# M_FOC.net
KiCad netlist of a schematic drawn in Altium Designer
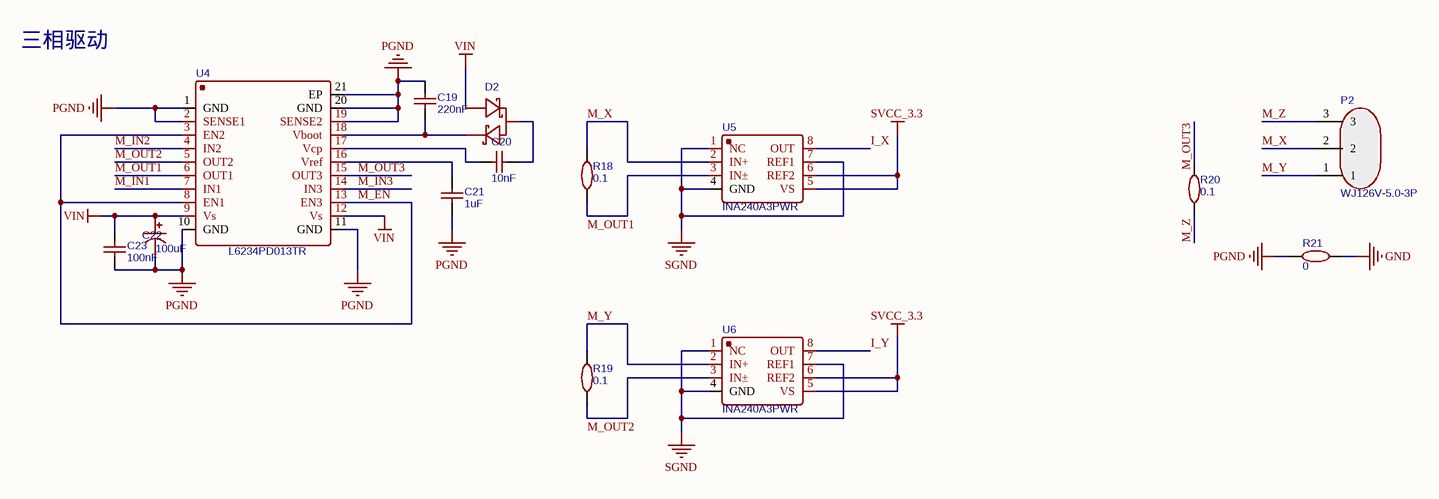
[diagram p0: M_FOC.SchDoc]

(export (version "E")
  (design (tool "Eeschema 10.0.6"))
  (components
    (comp (ref "C19")
      (value "220nF")
      (footprint "C0603")
      (fields
        (field (name "BOM_MANUFACTURER PART") "CC0805KRX7R9BB104")
        (field (name "BOM_SUPPLIER PART") "C49678")
      )
      (libsource (lib "FOC") (part "220nF"))
    )
    (comp (ref "C20")
      (value "10nF")
      (footprint "C0603")
      (fields
        (field (name "BOM_MANUFACTURER PART") "CC0805KRX7R9BB104")
        (field (name "BOM_SUPPLIER PART") "C49678")
      )
      (libsource (lib "FOC") (part "10nF"))
    )
    (comp (ref "C21")
      (value "1uF")
      (footprint "C0603")
      (fields
        (field (name "BOM_MANUFACTURER PART") "CC0805KRX7R9BB104")
        (field (name "BOM_SUPPLIER PART") "C49678")
      )
      (libsource (lib "FOC") (part "1uF"))
    )
    (comp (ref "C22")
      (value "100uF")
      (footprint "CAP-SMD_BD6.3-L6.6-W6.6-RD")
      (description "电解电容")
      (fields
        (field (name "BOM_MANUFACTURER PART") "RVE1V101M0607")
        (field (name "BOM_SUPPLIER PART") "C99837")
      )
      (libsource (lib "FOC") (part "100uF"))
    )
    (comp (ref "C23")
      (value "100nF")
      (footprint "C0603")
      (fields
        (field (name "BOM_MANUFACTURER PART") "CC0805KRX7R9BB104")
        (field (name "BOM_SUPPLIER PART") "C49678")
      )
      (libsource (lib "FOC") (part "100nF"))
    )
    (comp (ref "D2")
      (value "BAT54S_C916425")
      (footprint "SOT-23-3_L2.9-W1.3-P1.90-LS2.4-BR")
      (description "肖特基")
      (fields
        (field (name "BOM_SUPPLIER PART") "C916425")
        (field (name "BOM_MANUFACTURER PART") "BAT54S")
        (field (name "CONTRIBUTOR") "LCSC")
      )
      (libsource (lib "FOC") (part "BAT54S"))
    )
    (comp (ref "P2")
      (value "WJ126V-5.0-3P")
      (footprint "CONN-TH_3P-P5.00_WJ126V-5.0-3P")
      (fields (field (name "BOM_SUPPLIER PART") "C8401"))
      (libsource (lib "FOC") (part "WJ126V-5.0-3P"))
    )
    (comp (ref "R18")
      (value "0.1")
      (footprint "R2010")
      (fields
        (field (name "BOM_MANUFACTURER PART") "0805W8F1002T5E")
        (field (name "BOM_SUPPLIER PART") "C17414")
      )
      (libsource (lib "FOC") (part "0.1"))
    )
    (comp (ref "R19")
      (value "0.1")
      (footprint "R2010")
      (fields
        (field (name "BOM_MANUFACTURER PART") "0805W8F1002T5E")
        (field (name "BOM_SUPPLIER PART") "C17414")
      )
      (libsource (lib "FOC") (part "0.1"))
    )
    (comp (ref "R20")
      (value "0.1")
      (footprint "R2010")
      (fields
        (field (name "BOM_MANUFACTURER PART") "0805W8F1002T5E")
        (field (name "BOM_SUPPLIER PART") "C17414")
      )
      (libsource (lib "FOC") (part "0.1"))
    )
    (comp (ref "R21")
      (value "0")
      (footprint "R0603")
      (description "0欧电阻")
      (fields
        (field (name "BOM_MANUFACTURER PART") "0805W8F1002T5E")
        (field (name "BOM_SUPPLIER PART") "C17414")
      )
      (libsource (lib "FOC") (part "0"))
    )
    (comp (ref "U4")
      (value "L6234PD013TR")
      (footprint "POWERSO20_L15.9-W11.0-P1.27-LS14.2-BL-EP")
      (description "三路H桥")
      (fields (field (name "BOM_SUPPLIER PART") "C77581"))
      (libsource (lib "FOC") (part "L6234PD013TR"))
    )
    (comp (ref "U5")
      (value "INA240A3PWR")
      (footprint "TSSOP-8_L4.4-W3.0-P0.65-LS6.4-BL-2")
      (fields (field (name "BOM_SUPPLIER PART") "C544538") (field (name "CONTRIBUTOR") "LCSC"))
      (libsource (lib "FOC") (part "INA240A3PWR"))
    )
    (comp (ref "U6")
      (value "INA240A3PWR")
      (footprint "TSSOP-8_L4.4-W3.0-P0.65-LS6.4-BL-2")
      (fields (field (name "BOM_SUPPLIER PART") "C544538") (field (name "CONTRIBUTOR") "LCSC"))
      (libsource (lib "FOC") (part "INA240A3PWR"))
    )
  )
  (nets
    (net (code "2") (name "/I_X") (class "Default")
      (node (ref "U5") (pin "8") (pinfunction "OUT_8") (pintype "passive"))
    )
    (net (code "3") (name "/I_Y") (class "Default")
      (node (ref "U6") (pin "8") (pinfunction "OUT_8") (pintype "passive"))
    )
    (net (code "4") (name "/M_EN") (class "Default")
      (node (ref "U4") (pin "13") (pinfunction "EN3_13") (pintype "passive"))
      (node (ref "U4") (pin "3") (pinfunction "EN2_3") (pintype "passive"))
      (node (ref "U4") (pin "8") (pinfunction "EN1_8") (pintype "passive"))
    )
    (net (code "5") (name "/M_IN1") (class "Default")
      (node (ref "U4") (pin "7") (pinfunction "IN1_7") (pintype "passive"))
    )
    (net (code "6") (name "/M_IN2") (class "Default")
      (node (ref "U4") (pin "4") (pinfunction "IN2_4") (pintype "passive"))
    )
    (net (code "7") (name "/M_IN3") (class "Default")
      (node (ref "U4") (pin "14") (pinfunction "IN3_14") (pintype "passive"))
    )
    (net (code "8") (name "/M_OUT1") (class "Default")
      (node (ref "R18") (pin "1") (pinfunction "1_1") (pintype "passive"))
      (node (ref "U4") (pin "6") (pinfunction "OUT1_6") (pintype "passive"))
      (node (ref "U5") (pin "3") (pinfunction "IN±_3") (pintype "passive"))
    )
    (net (code "9") (name "/M_OUT2") (class "Default")
      (node (ref "R19") (pin "1") (pinfunction "1_1") (pintype "passive"))
      (node (ref "U4") (pin "5") (pinfunction "OUT2_5") (pintype "passive"))
      (node (ref "U6") (pin "3") (pinfunction "IN±_3") (pintype "passive"))
    )
    (net (code "10") (name "/M_OUT3") (class "Default")
      (node (ref "R20") (pin "2") (pinfunction "2_2") (pintype "passive"))
      (node (ref "U4") (pin "15") (pinfunction "OUT3_15") (pintype "passive"))
    )
    (net (code "11") (name "/M_X") (class "Default")
      (node (ref "P2") (pin "2") (pinfunction "2_2") (pintype "passive"))
      (node (ref "R18") (pin "2") (pinfunction "2_2") (pintype "passive"))
      (node (ref "U5") (pin "2") (pinfunction "IN+_2") (pintype "passive"))
    )
    (net (code "12") (name "/M_Y") (class "Default")
      (node (ref "P2") (pin "1") (pinfunction "1_1") (pintype "passive"))
      (node (ref "R19") (pin "2") (pinfunction "2_2") (pintype "passive"))
      (node (ref "U6") (pin "2") (pinfunction "IN+_2") (pintype "passive"))
    )
    (net (code "13") (name "/M_Z") (class "Default")
      (node (ref "P2") (pin "3") (pinfunction "3_3") (pintype "passive"))
      (node (ref "R20") (pin "1") (pinfunction "1_1") (pintype "passive"))
    )
    (net (code "14") (name "GND") (class "Default")
      (node (ref "R21") (pin "2") (pinfunction "2_2") (pintype "passive"))
    )
    (net (code "15") (name "Net-(C20-Pad2)") (class "Default")
      (node (ref "C20") (pin "2") (pinfunction "2_2") (pintype "passive"))
      (node (ref "D2") (pin "3") (pinfunction "3_3") (pintype "passive"))
    )
    (net (code "16") (name "Net-(D2-K)") (class "Default")
      (node (ref "C19") (pin "1") (pinfunction "1_1") (pintype "passive"))
      (node (ref "D2") (pin "2") (pinfunction "K_2") (pintype "passive"))
      (node (ref "U4") (pin "18") (pinfunction "Vboot_18") (pintype "passive"))
    )
    (net (code "17") (name "Net-(U4-Vcp)") (class "Default")
      (node (ref "C20") (pin "1") (pinfunction "1_1") (pintype "passive"))
      (node (ref "U4") (pin "17") (pinfunction "Vcp_17") (pintype "passive"))
    )
    (net (code "18") (name "Net-(U4-Vref)") (class "Default")
      (node (ref "C21") (pin "2") (pinfunction "2_2") (pintype "passive"))
      (node (ref "U4") (pin "16") (pinfunction "Vref_16") (pintype "passive"))
    )
    (net (code "19") (name "PGND") (class "Default")
      (node (ref "C19") (pin "2") (pinfunction "2_2") (pintype "passive"))
      (node (ref "C21") (pin "1") (pinfunction "1_1") (pintype "passive"))
      (node (ref "C22") (pin "2") (pinfunction "2_2") (pintype "passive"))
      (node (ref "C23") (pin "1") (pinfunction "1_1") (pintype "passive"))
      (node (ref "R21") (pin "1") (pinfunction "1_1") (pintype "passive"))
      (node (ref "U4") (pin "1") (pinfunction "GND_1") (pintype "passive"))
      (node (ref "U4") (pin "10") (pinfunction "GND_10") (pintype "passive"))
      (node (ref "U4") (pin "11") (pinfunction "GND_11") (pintype "passive"))
      (node (ref "U4") (pin "19") (pinfunction "SENSE2_19") (pintype "passive"))
      (node (ref "U4") (pin "2") (pinfunction "SENSE1_2") (pintype "passive"))
      (node (ref "U4") (pin "20") (pinfunction "GND_20") (pintype "passive"))
      (node (ref "U4") (pin "21") (pinfunction "EP_21") (pintype "passive"))
    )
    (net (code "20") (name "SGND") (class "Default")
      (node (ref "U5") (pin "1") (pinfunction "NC_1") (pintype "passive"))
      (node (ref "U5") (pin "4") (pinfunction "GND_4") (pintype "passive"))
      (node (ref "U5") (pin "7") (pinfunction "REF1_7") (pintype "passive"))
      (node (ref "U6") (pin "1") (pinfunction "NC_1") (pintype "passive"))
      (node (ref "U6") (pin "4") (pinfunction "GND_4") (pintype "passive"))
      (node (ref "U6") (pin "7") (pinfunction "REF1_7") (pintype "passive"))
    )
    (net (code "21") (name "SVCC_3.3") (class "Default")
      (node (ref "U5") (pin "5") (pinfunction "VS_5") (pintype "passive"))
      (node (ref "U5") (pin "6") (pinfunction "REF2_6") (pintype "passive"))
      (node (ref "U6") (pin "5") (pinfunction "VS_5") (pintype "passive"))
      (node (ref "U6") (pin "6") (pinfunction "REF2_6") (pintype "passive"))
    )
    (net (code "22") (name "VIN") (class "Default")
      (node (ref "C22") (pin "1") (pinfunction "1_1") (pintype "passive"))
      (node (ref "C23") (pin "2") (pinfunction "2_2") (pintype "passive"))
      (node (ref "D2") (pin "1") (pinfunction "A_1") (pintype "passive"))
      (node (ref "U4") (pin "12") (pinfunction "Vs_12") (pintype "passive"))
      (node (ref "U4") (pin "9") (pinfunction "Vs_9") (pintype "passive"))
    )
  )
)
